# Conning_Tower.net
KiCad netlist of a schematic drawn in Altium Designer
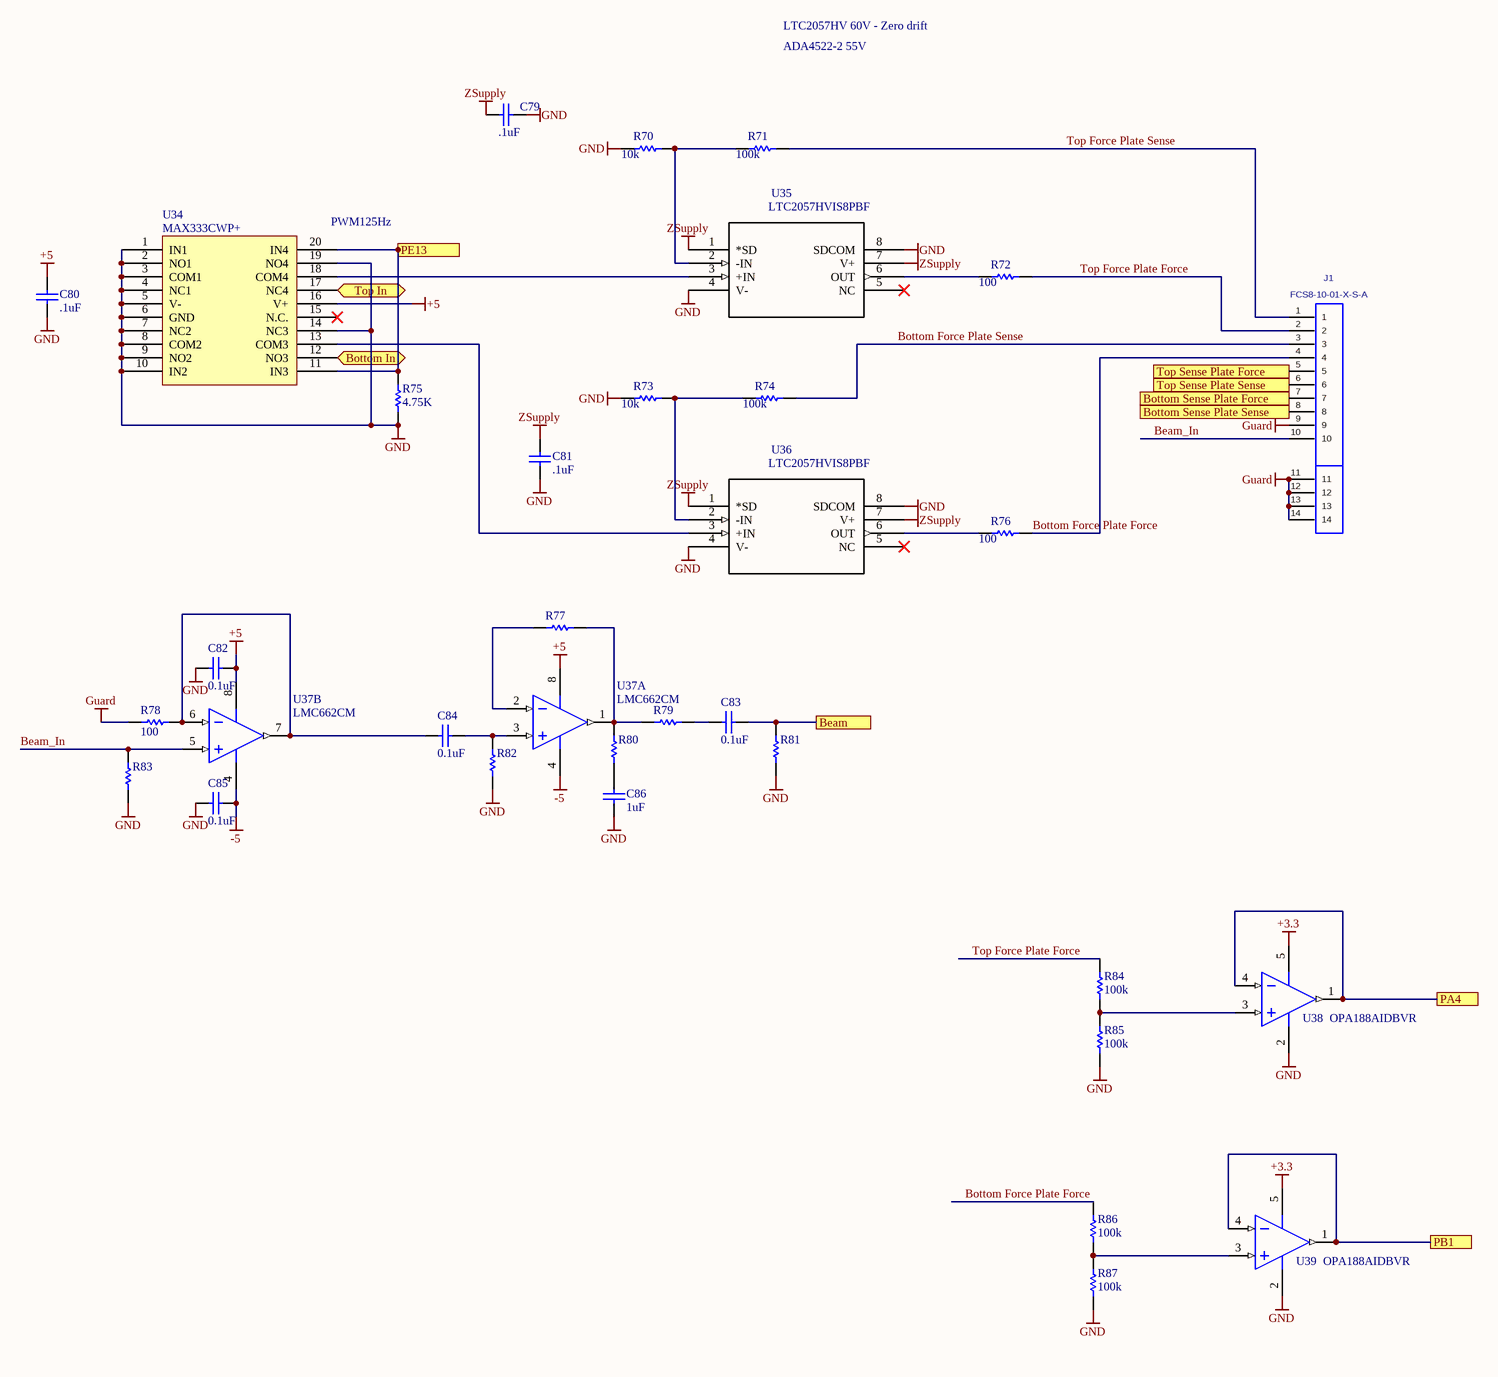
[diagram p0: Conning_Tower.SchDoc]

(export (version "E")
  (design (tool "Eeschema 10.0.6"))
  (components
    (comp (ref "C79")
      (value ".1uF")
      (footprint "CAPC0805(2012)75_M")
      (description "CAP 33pF 25V ±2% 0805 (2012 Metric) Thickness 0.75mm SMD")
      (fields (field (name "TOLERANCE") "Â±2%"))
      (libsource (lib "Altium Content Vault") (part "CMP-1036-01414-1"))
    )
    (comp (ref "C80")
      (value ".1uF")
      (footprint "CAPC0805(2012)75_L")
      (description "CAP 150pF 16V ±10% 0805 (2012 Metric) Thickness 0.75mm SMD")
      (fields (field (name "TOLERANCE") "Â±10%"))
      (libsource (lib "Altium Content Vault") (part "CMP-1036-02117-1"))
    )
    (comp (ref "C81")
      (value ".1uF")
      (footprint "CAPC0805(2012)75_M")
      (description "CAP 33pF 25V ±2% 0805 (2012 Metric) Thickness 0.75mm SMD")
      (fields (field (name "TOLERANCE") "Â±2%"))
      (libsource (lib "Altium Content Vault") (part "CMP-1036-01414-1"))
    )
    (comp (ref "C82")
      (value "0.1uF")
      (footprint "CAPC0402(1005)60_L")
      (description "CAP CER 0.1UF 10V X7R 0402")
      (fields
        (field (name "MANUFACTURER") "Murata Electronics North America")
        (field (name "MANUFACTURER PART NUMBER") "GRM155R71A104KA01D")
      )
      (libsource (lib "Altium Content Vault") (part "CMP-1034-00252-1"))
    )
    (comp (ref "C83")
      (value "0.1uF")
      (footprint "CAPC0402(1005)60_L")
      (description "CAP CER 0.1UF 10V X7R 0402")
      (fields
        (field (name "MANUFACTURER") "Murata Electronics North America")
        (field (name "MANUFACTURER PART NUMBER") "GRM155R71A104KA01D")
      )
      (libsource (lib "Altium Content Vault") (part "CMP-1034-00252-1"))
    )
    (comp (ref "C84")
      (value "0.1uF")
      (footprint "CAPC0402(1005)60_L")
      (description "CAP CER 0.1UF 10V X7R 0402")
      (fields
        (field (name "MANUFACTURER") "Murata Electronics North America")
        (field (name "MANUFACTURER PART NUMBER") "GRM155R71A104KA01D")
      )
      (libsource (lib "Altium Content Vault") (part "CMP-1034-00252-1"))
    )
    (comp (ref "C85")
      (value "0.1uF")
      (footprint "CAPC0402(1005)60_L")
      (description "CAP CER 0.1UF 10V X7R 0402")
      (fields
        (field (name "MANUFACTURER") "Murata Electronics North America")
        (field (name "MANUFACTURER PART NUMBER") "GRM155R71A104KA01D")
      )
      (libsource (lib "Altium Content Vault") (part "CMP-1034-00252-1"))
    )
    (comp (ref "C86")
      (value "1uF")
      (footprint "CAPC0402(1005)60_L")
      (description "CAP CER 0.1UF 10V X7R 0402")
      (fields
        (field (name "MANUFACTURER") "Murata Electronics North America")
        (field (name "MANUFACTURER PART NUMBER") "GRM155R71A104KA01D")
      )
      (libsource (lib "Altium Content Vault") (part "CMP-1034-00252-1"))
    )
    (comp (ref "J1")
      (value "FCS8-10-01-X-S-A")
      (footprint "FCS8-10-01-X-S-A")
      (description "FCS8 Socket Assembly, 20-Pins, w/ Alignment Pins")
      (fields (field (name "MANUFACTURER") "SAMTEC") (field (name "CREATED") "31 NOV 2013 - WENDY XIN"))
      (libsource (lib "FCS8-10-01-X-S-A") (part "FCS8-10-01-X-S-A"))
    )
    (comp (ref "R70")
      (value "10k")
      (footprint "RESC0402(1005)_M")
      (description "10k 0.063W 1% 0402 (1005 Metric)  SMD")
      (fields (field (name "POWER") "0.063 W") (field (name "TOLERANCE") "1 %"))
      (libsource (lib "Altium Content Vault") (part "RES"))
    )
    (comp (ref "R71")
      (value "100k")
      (footprint "RESC0402(1005)_M")
      (description "100k 0.063W 1% 0402 (1005 Metric)  SMD")
      (fields (field (name "POWER") "0.063 W") (field (name "TOLERANCE") "1 %"))
      (libsource (lib "Altium Content Vault") (part "RES"))
    )
    (comp (ref "R72")
      (value "100")
      (footprint "RESC0402(1005)_M")
      (description "6M34 0.063W 1% 0402 (1005 Metric)  SMD")
      (fields (field (name "POWER") "0.063 W") (field (name "TOLERANCE") "1 %"))
      (libsource (lib "Altium Content Vault") (part "RES"))
    )
    (comp (ref "R73")
      (value "10k")
      (footprint "RESC0402(1005)_M")
      (description "10k 0.063W 1% 0402 (1005 Metric)  SMD")
      (fields (field (name "POWER") "0.063 W") (field (name "TOLERANCE") "1 %"))
      (libsource (lib "Altium Content Vault") (part "RES"))
    )
    (comp (ref "R74")
      (value "100k")
      (footprint "RESC0402(1005)_M")
      (description "100k 0.063W 1% 0402 (1005 Metric)  SMD")
      (fields (field (name "POWER") "0.063 W") (field (name "TOLERANCE") "1 %"))
      (libsource (lib "Altium Content Vault") (part "RES"))
    )
    (comp (ref "R75")
      (value "4.75K")
      (footprint "RESC0805(2012)_L")
      (description "2R55 0.125W 1% 0805 (2012 Metric)  SMD")
      (fields (field (name "TOLERANCE") "1 %") (field (name "POWER") "0.125 W"))
      (libsource (lib "Altium Content Vault") (part "CMP-1013-00215-1"))
    )
    (comp (ref "R76")
      (value "100")
      (footprint "RESC0402(1005)_M")
      (description "6M34 0.063W 1% 0402 (1005 Metric)  SMD")
      (fields (field (name "POWER") "0.063 W") (field (name "TOLERANCE") "1 %"))
      (libsource (lib "Altium Content Vault") (part "RES"))
    )
    (comp (ref "R77")
      (value "~")
      (footprint "RESC0402(1005)_M")
      (libsource (lib "Altium Content Vault") (part "CMP-1011-00463-1"))
    )
    (comp (ref "R78")
      (value "100")
      (footprint "RESC0402(1005)_M")
      (libsource (lib "Altium Content Vault") (part "CMP-1011-00463-1"))
    )
    (comp (ref "R79")
      (value "~")
      (footprint "RESC0402(1005)_M")
      (libsource (lib "Altium Content Vault") (part "CMP-1011-00463-1"))
    )
    (comp (ref "R80")
      (value "~")
      (footprint "RESC0402(1005)_M")
      (libsource (lib "Altium Content Vault") (part "CMP-1011-00463-1"))
    )
    (comp (ref "R81")
      (value "~")
      (footprint "RESC0402(1005)_M")
      (libsource (lib "Altium Content Vault") (part "CMP-1011-00463-1"))
    )
    (comp (ref "R82")
      (value "~")
      (footprint "RESC0402(1005)_M")
      (libsource (lib "Altium Content Vault") (part "CMP-1011-00463-1"))
    )
    (comp (ref "R83")
      (value "~")
      (footprint "RESC0402(1005)_M")
      (libsource (lib "Altium Content Vault") (part "CMP-1011-00463-1"))
    )
    (comp (ref "R84")
      (value "100k")
      (footprint "RESC0402(1005)_M")
      (description "100k 0.063W 1% 0402 (1005 Metric)  SMD")
      (fields (field (name "POWER") "0.063 W") (field (name "TOLERANCE") "1 %"))
      (libsource (lib "Altium Content Vault") (part "RES"))
    )
    (comp (ref "R85")
      (value "100k")
      (footprint "RESC0402(1005)_M")
      (description "100k 0.063W 1% 0402 (1005 Metric)  SMD")
      (fields (field (name "POWER") "0.063 W") (field (name "TOLERANCE") "1 %"))
      (libsource (lib "Altium Content Vault") (part "RES"))
    )
    (comp (ref "R86")
      (value "100k")
      (footprint "RESC0402(1005)_M")
      (description "100k 0.063W 1% 0402 (1005 Metric)  SMD")
      (fields (field (name "POWER") "0.063 W") (field (name "TOLERANCE") "1 %"))
      (libsource (lib "Altium Content Vault") (part "RES"))
    )
    (comp (ref "R87")
      (value "100k")
      (footprint "RESC0402(1005)_M")
      (description "100k 0.063W 1% 0402 (1005 Metric)  SMD")
      (fields (field (name "POWER") "0.063 W") (field (name "TOLERANCE") "1 %"))
      (libsource (lib "Altium Content Vault") (part "RES"))
    )
    (comp (ref "U34")
      (value "MAX333CWP+")
      (footprint "TSOP65P640X90-20N")
      (description "IC SWITCH QUAD SPDT 20TSSOP")
      (fields (field (name "MANUFACTURER") "Maxim") (field (name "MANUFACTURER PART NUMBER") "MAX333AEUP+"))
      (libsource (lib "ZLS_Schematic_lib") (part "MAX333CWP+"))
    )
    (comp (ref "U35")
      (value "LTC2057HVIS8PBF")
      (footprint "*SO-8_S")
      (description "LTC2057/LTC2057HV - High Voltage, Low Noise Zero-Drift Operational Amplifier")
      (fields
        (field (name "MF") "Linear Technology/Analog")
        (field (name "DIGI-KEY_PART_NUMBER") "LTC2057HVIS8#PBF-ND")
      )
      (libsource (lib "LTC2057HVIS8PBF") (part "LTC2057HVIS8PBF"))
    )
    (comp (ref "U36")
      (value "LTC2057HVIS8PBF")
      (footprint "*SO-8_S")
      (description "LTC2057/LTC2057HV - High Voltage, Low Noise Zero-Drift Operational Amplifier")
      (fields
        (field (name "MF") "Linear Technology/Analog")
        (field (name "DIGI-KEY_PART_NUMBER") "LTC2057HVIS8#PBF-ND")
      )
      (libsource (lib "LTC2057HVIS8PBF") (part "LTC2057HVIS8PBF"))
    )
    (comp (ref "U37")
      (value "LMC662CM")
      (footprint "D0008A_M")
      (description "CMOS Dual Operational Amplifier, 8-pin Narrow SOIC")
      (fields (field (name "MANUFACTURER") "Texas Instruments"))
      (libsource (lib "Altium Content Vault") (part "AMP-OPA-LF353-8"))
    )
    (comp (ref "U38")
      (value "OPA188AIDBVR")
      (footprint "DBV0005A_M")
      (fields (field (name "MANUFACTURER") "Texas Instruments"))
      (libsource (lib "Altium Content Vault") (part "CMP-0809-00005-2"))
    )
    (comp (ref "U39")
      (value "OPA188AIDBVR")
      (footprint "DBV0005A_M")
      (fields (field (name "MANUFACTURER") "Texas Instruments"))
      (libsource (lib "Altium Content Vault") (part "CMP-0809-00005-2"))
    )
  )
  (nets
    (net (code "1") (name "+3.3") (class "Default")
      (node (ref "U38") (pin "5") (pinfunction "V+_5") (pintype "power_in"))
      (node (ref "U39") (pin "5") (pinfunction "V+_5") (pintype "power_in"))
    )
    (net (code "2") (name "+5") (class "Default")
      (node (ref "C80") (pin "2") (pinfunction "2_2") (pintype "passive"))
      (node (ref "C82") (pin "2") (pinfunction "2_2") (pintype "passive"))
      (node (ref "U34") (pin "16") (pinfunction "V+_16") (pintype "power_in"))
      (node (ref "U37") (pin "8") (pinfunction "V+_8") (pintype "power_in"))
    )
    (net (code "3") (name "-5") (class "Default")
      (node (ref "C85") (pin "2") (pinfunction "2_2") (pintype "passive"))
      (node (ref "U37") (pin "4") (pinfunction "V-_4") (pintype "power_in"))
    )
    (net (code "4") (name "/Beam") (class "Default")
      (node (ref "C83") (pin "2") (pinfunction "2_2") (pintype "passive"))
      (node (ref "R81") (pin "1") (pinfunction "1_1") (pintype "passive"))
    )
    (net (code "5") (name "/Beam_In") (class "Default")
      (node (ref "J1") (pin "10") (pinfunction "10_10") (pintype "passive"))
      (node (ref "R83") (pin "2") (pinfunction "2_2") (pintype "passive"))
      (node (ref "U37") (pin "5") (pinfunction "INB+_5") (pintype "input"))
    )
    (net (code "6") (name "/Bottom Force Plate Force") (class "Default")
      (node (ref "J1") (pin "4") (pinfunction "4_4") (pintype "passive"))
      (node (ref "R76") (pin "2") (pinfunction "2_2") (pintype "passive"))
      (node (ref "R86") (pin "2") (pinfunction "2_2") (pintype "passive"))
    )
    (net (code "7") (name "/Bottom Force Plate Sense") (class "Default")
      (node (ref "J1") (pin "3") (pinfunction "3_3") (pintype "passive"))
      (node (ref "R74") (pin "2") (pinfunction "2_2") (pintype "passive"))
    )
    (net (code "8") (name "/Bottom In") (class "Default")
      (node (ref "U34") (pin "12") (pinfunction "NO3_12") (pintype "passive"))
    )
    (net (code "9") (name "/Bottom Sense Plate Force") (class "Default")
      (node (ref "J1") (pin "7") (pinfunction "7_7") (pintype "passive"))
    )
    (net (code "10") (name "/Bottom Sense Plate Sense") (class "Default")
      (node (ref "J1") (pin "8") (pinfunction "8_8") (pintype "passive"))
    )
    (net (code "11") (name "/PA4") (class "Default")
      (node (ref "U38") (pin "1") (pinfunction "OUT_1") (pintype "output"))
      (node (ref "U38") (pin "4") (pinfunction "IN-_4") (pintype "input"))
    )
    (net (code "12") (name "/PB1") (class "Default")
      (node (ref "U39") (pin "1") (pinfunction "OUT_1") (pintype "output"))
      (node (ref "U39") (pin "4") (pinfunction "IN-_4") (pintype "input"))
    )
    (net (code "13") (name "/PE13") (class "Default")
      (node (ref "R75") (pin "1") (pinfunction "1_1") (pintype "passive"))
      (node (ref "U34") (pin "11") (pinfunction "IN3_11") (pintype "passive"))
      (node (ref "U34") (pin "20") (pinfunction "IN4_20") (pintype "passive"))
    )
    (net (code "14") (name "/Top Force Plate Force") (class "Default")
      (node (ref "J1") (pin "2") (pinfunction "2_2") (pintype "passive"))
      (node (ref "R72") (pin "2") (pinfunction "2_2") (pintype "passive"))
      (node (ref "R84") (pin "2") (pinfunction "2_2") (pintype "passive"))
    )
    (net (code "15") (name "/Top Force Plate Sense") (class "Default")
      (node (ref "J1") (pin "1") (pinfunction "1_1") (pintype "passive"))
      (node (ref "R71") (pin "2") (pinfunction "2_2") (pintype "passive"))
    )
    (net (code "16") (name "/Top In") (class "Default")
      (node (ref "U34") (pin "17") (pinfunction "NC4_17") (pintype "passive"))
    )
    (net (code "17") (name "/Top Sense Plate Force") (class "Default")
      (node (ref "J1") (pin "5") (pinfunction "5_5") (pintype "passive"))
    )
    (net (code "18") (name "/Top Sense Plate Sense") (class "Default")
      (node (ref "J1") (pin "6") (pinfunction "6_6") (pintype "passive"))
    )
    (net (code "19") (name "GND") (class "Default")
      (node (ref "C79") (pin "2") (pinfunction "2_2") (pintype "passive"))
      (node (ref "C80") (pin "1") (pinfunction "1_1") (pintype "passive"))
      (node (ref "C81") (pin "1") (pinfunction "1_1") (pintype "passive"))
      (node (ref "C82") (pin "1") (pinfunction "1_1") (pintype "passive"))
      (node (ref "C85") (pin "1") (pinfunction "1_1") (pintype "passive"))
      (node (ref "C86") (pin "1") (pinfunction "1_1") (pintype "passive"))
      (node (ref "R70") (pin "1") (pinfunction "1_1") (pintype "passive"))
      (node (ref "R73") (pin "1") (pinfunction "1_1") (pintype "passive"))
      (node (ref "R75") (pin "2") (pinfunction "2_2") (pintype "passive"))
      (node (ref "R81") (pin "2") (pinfunction "2_2") (pintype "passive"))
      (node (ref "R82") (pin "2") (pinfunction "2_2") (pintype "passive"))
      (node (ref "R83") (pin "1") (pinfunction "1_1") (pintype "passive"))
      (node (ref "R85") (pin "1") (pinfunction "1_1") (pintype "passive"))
      (node (ref "R87") (pin "1") (pinfunction "1_1") (pintype "passive"))
      (node (ref "U34") (pin "1") (pinfunction "IN1_1") (pintype "passive"))
      (node (ref "U34") (pin "10") (pinfunction "IN2_10") (pintype "passive"))
      (node (ref "U34") (pin "14") (pinfunction "NC3_14") (pintype "passive"))
      (node (ref "U34") (pin "19") (pinfunction "NO4_19") (pintype "passive"))
      (node (ref "U34") (pin "2") (pinfunction "NO1_2") (pintype "passive"))
      (node (ref "U34") (pin "3") (pinfunction "COM1_3") (pintype "passive"))
      (node (ref "U34") (pin "4") (pinfunction "NC1_4") (pintype "passive"))
      (node (ref "U34") (pin "5") (pinfunction "V-_5") (pintype "power_in"))
      (node (ref "U34") (pin "6") (pinfunction "GND_6") (pintype "passive"))
      (node (ref "U34") (pin "7") (pinfunction "NC2_7") (pintype "passive"))
      (node (ref "U34") (pin "8") (pinfunction "COM2_8") (pintype "passive"))
      (node (ref "U34") (pin "9") (pinfunction "NO2_9") (pintype "passive"))
      (node (ref "U35") (pin "4") (pinfunction "V-_4") (pintype "power_in"))
      (node (ref "U35") (pin "8") (pinfunction "SDCOM_8") (pintype "passive"))
      (node (ref "U36") (pin "4") (pinfunction "V-_4") (pintype "power_in"))
      (node (ref "U36") (pin "8") (pinfunction "SDCOM_8") (pintype "passive"))
      (node (ref "U38") (pin "2") (pinfunction "V-_2") (pintype "power_in"))
      (node (ref "U39") (pin "2") (pinfunction "V-_2") (pintype "power_in"))
    )
    (net (code "20") (name "Guard") (class "Default")
      (node (ref "J1") (pin "11") (pinfunction "11_11") (pintype "passive"))
      (node (ref "J1") (pin "12") (pinfunction "12_12") (pintype "passive"))
      (node (ref "J1") (pin "13") (pinfunction "13_13") (pintype "passive"))
      (node (ref "J1") (pin "14") (pinfunction "14_14") (pintype "passive"))
      (node (ref "J1") (pin "9") (pinfunction "9_9") (pintype "passive"))
      (node (ref "R78") (pin "2") (pinfunction "2_2") (pintype "passive"))
    )
    (net (code "21") (name "Net-(C83-Pad1)") (class "Default")
      (node (ref "C83") (pin "1") (pinfunction "1_1") (pintype "passive"))
      (node (ref "R79") (pin "1") (pinfunction "1_1") (pintype "passive"))
    )
    (net (code "22") (name "Net-(C86-Pad2)") (class "Default")
      (node (ref "C86") (pin "2") (pinfunction "2_2") (pintype "passive"))
      (node (ref "R80") (pin "2") (pinfunction "2_2") (pintype "passive"))
    )
    (net (code "23") (name "Net-(U34-COM3)") (class "Default")
      (node (ref "U34") (pin "13") (pinfunction "COM3_13") (pintype "passive"))
      (node (ref "U36") (pin "3") (pinfunction "+IN_3") (pintype "input"))
    )
    (net (code "24") (name "Net-(U34-COM4)") (class "Default")
      (node (ref "U34") (pin "18") (pinfunction "COM4_18") (pintype "passive"))
      (node (ref "U35") (pin "3") (pinfunction "+IN_3") (pintype "input"))
    )
    (net (code "25") (name "Net-(U35--IN)") (class "Default")
      (node (ref "R70") (pin "2") (pinfunction "2_2") (pintype "passive"))
      (node (ref "R71") (pin "1") (pinfunction "1_1") (pintype "passive"))
      (node (ref "U35") (pin "2") (pinfunction "-IN_2") (pintype "input"))
    )
    (net (code "26") (name "Net-(U35-OUT)") (class "Default")
      (node (ref "R72") (pin "1") (pinfunction "1_1") (pintype "passive"))
      (node (ref "U35") (pin "6") (pinfunction "OUT_6") (pintype "output"))
    )
    (net (code "27") (name "Net-(U36--IN)") (class "Default")
      (node (ref "R73") (pin "2") (pinfunction "2_2") (pintype "passive"))
      (node (ref "R74") (pin "1") (pinfunction "1_1") (pintype "passive"))
      (node (ref "U36") (pin "2") (pinfunction "-IN_2") (pintype "input"))
    )
    (net (code "28") (name "Net-(U36-OUT)") (class "Default")
      (node (ref "R76") (pin "1") (pinfunction "1_1") (pintype "passive"))
      (node (ref "U36") (pin "6") (pinfunction "OUT_6") (pintype "output"))
    )
    (net (code "29") (name "Net-(U37A-INA+)") (class "Default")
      (node (ref "C84") (pin "2") (pinfunction "2_2") (pintype "passive"))
      (node (ref "R82") (pin "1") (pinfunction "1_1") (pintype "passive"))
      (node (ref "U37") (pin "3") (pinfunction "INA+_3") (pintype "input"))
    )
    (net (code "30") (name "Net-(U37A-INA-)") (class "Default")
      (node (ref "R77") (pin "2") (pinfunction "2_2") (pintype "passive"))
      (node (ref "U37") (pin "2") (pinfunction "INA-_2") (pintype "input"))
    )
    (net (code "31") (name "Net-(U37A-OUTA)") (class "Default")
      (node (ref "R77") (pin "1") (pinfunction "1_1") (pintype "passive"))
      (node (ref "R79") (pin "2") (pinfunction "2_2") (pintype "passive"))
      (node (ref "R80") (pin "1") (pinfunction "1_1") (pintype "passive"))
      (node (ref "U37") (pin "1") (pinfunction "OUTA_1") (pintype "output"))
    )
    (net (code "32") (name "Net-(U37B-INB-)") (class "Default")
      (node (ref "C84") (pin "1") (pinfunction "1_1") (pintype "passive"))
      (node (ref "R78") (pin "1") (pinfunction "1_1") (pintype "passive"))
      (node (ref "U37") (pin "6") (pinfunction "INB-_6") (pintype "input"))
      (node (ref "U37") (pin "7") (pinfunction "OUTB_7") (pintype "output"))
    )
    (net (code "33") (name "Net-(U38-IN+)") (class "Default")
      (node (ref "R84") (pin "1") (pinfunction "1_1") (pintype "passive"))
      (node (ref "R85") (pin "2") (pinfunction "2_2") (pintype "passive"))
      (node (ref "U38") (pin "3") (pinfunction "IN+_3") (pintype "input"))
    )
    (net (code "34") (name "Net-(U39-IN+)") (class "Default")
      (node (ref "R86") (pin "1") (pinfunction "1_1") (pintype "passive"))
      (node (ref "R87") (pin "2") (pinfunction "2_2") (pintype "passive"))
      (node (ref "U39") (pin "3") (pinfunction "IN+_3") (pintype "input"))
    )
    (net (code "35") (name "ZSupply") (class "Default")
      (node (ref "C79") (pin "1") (pinfunction "1_1") (pintype "passive"))
      (node (ref "C81") (pin "2") (pinfunction "2_2") (pintype "passive"))
      (node (ref "U35") (pin "1") (pinfunction "*SD_1") (pintype "passive"))
      (node (ref "U35") (pin "7") (pinfunction "V+_7") (pintype "power_in"))
      (node (ref "U36") (pin "1") (pinfunction "*SD_1") (pintype "passive"))
      (node (ref "U36") (pin "7") (pinfunction "V+_7") (pintype "power_in"))
    )
    (net (code "36") (name "unconnected-(U34-N.C.-Pad15)") (class "Default")
      (node (ref "U34") (pin "15") (pinfunction "N.C._15") (pintype "passive+no_connect"))
    )
    (net (code "37") (name "unconnected-(U35-NC-Pad5)") (class "Default")
      (node (ref "U35") (pin "5") (pinfunction "NC_5") (pintype "passive+no_connect"))
    )
    (net (code "38") (name "unconnected-(U36-NC-Pad5)") (class "Default")
      (node (ref "U36") (pin "5") (pinfunction "NC_5") (pintype "passive+no_connect"))
    )
  )
)
